# CH32L103K8U-R0.net
KiCad netlist of a schematic drawn in Altium Designer
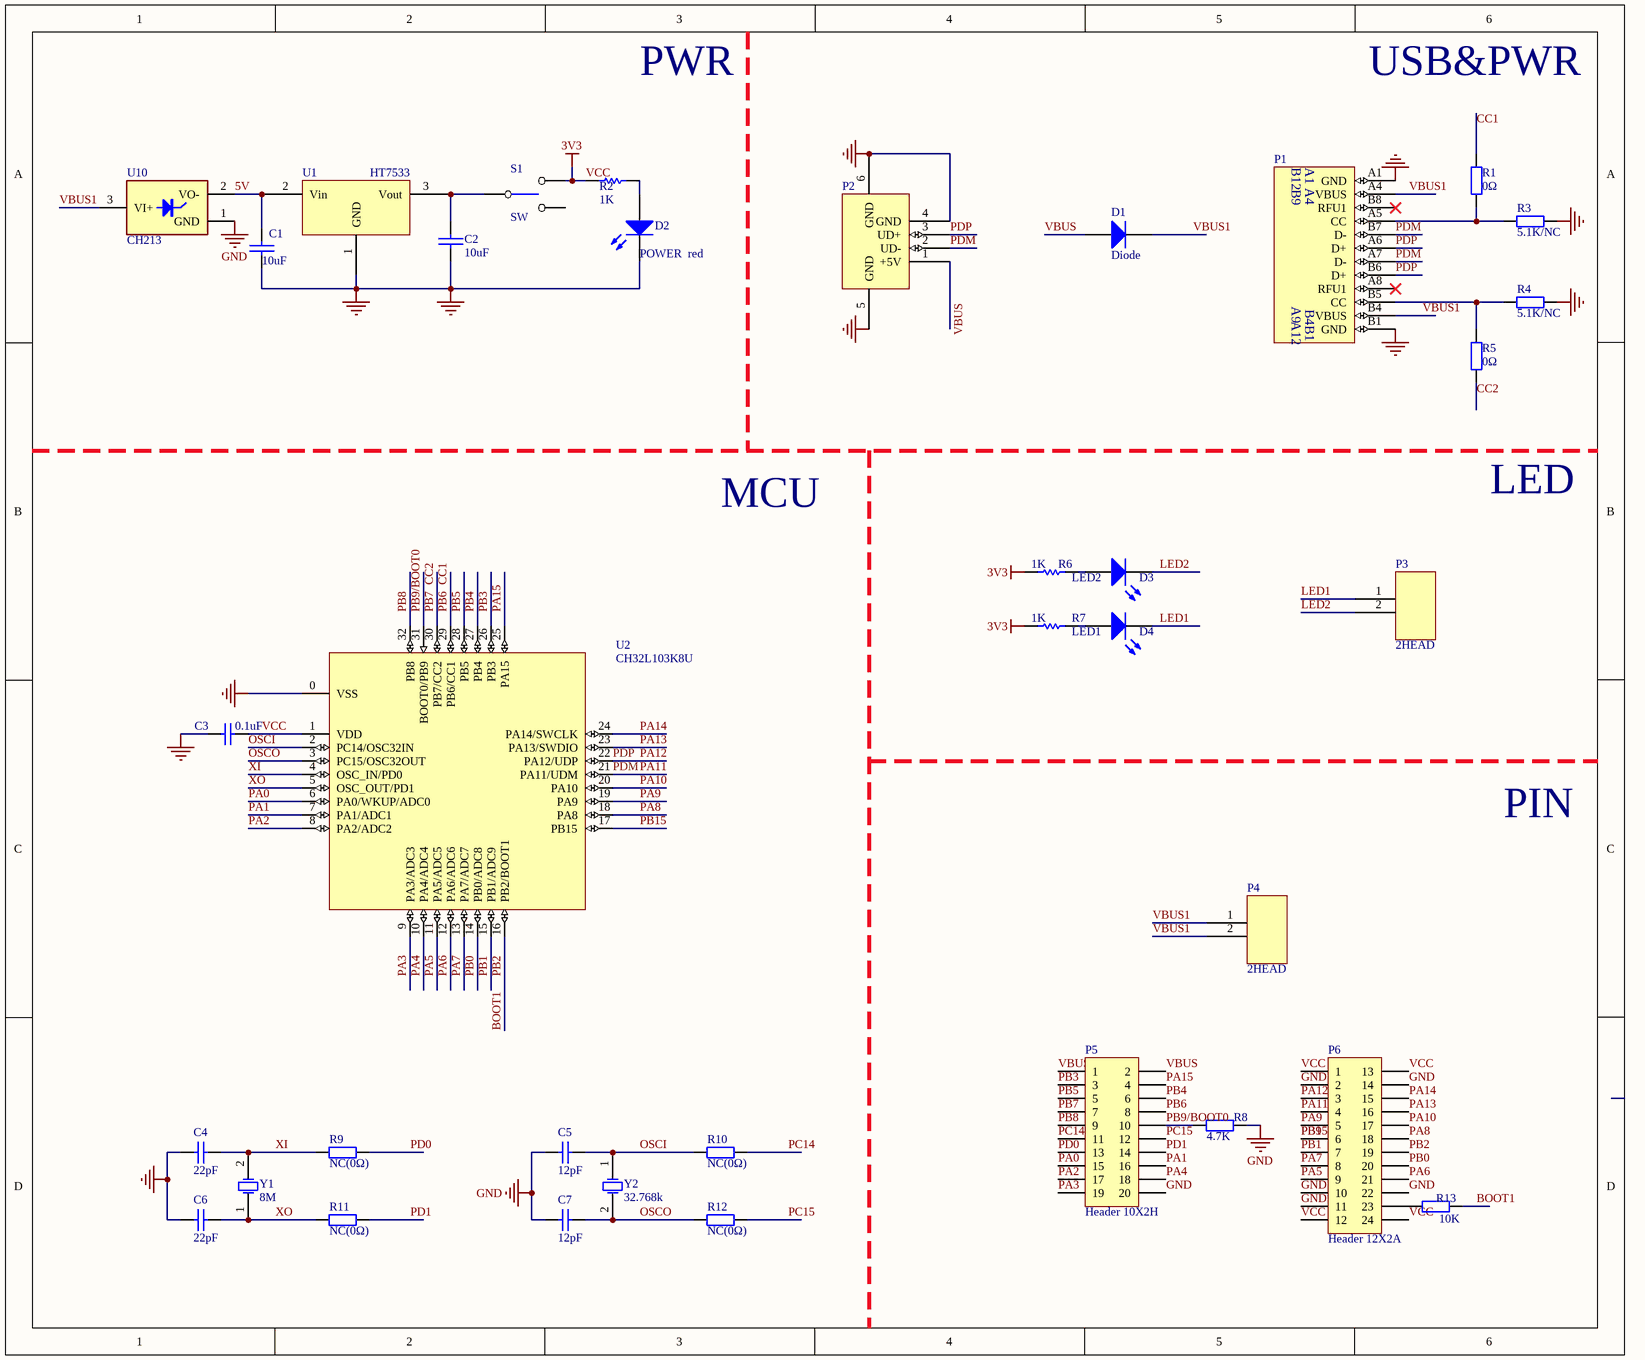
[diagram p0: CH32L103K8U-R0.SchDoc]

(export (version "E")
  (design (tool "Eeschema 10.0.6"))
  (components
    (comp (ref "C1")
      (value "10uF")
      (footprint "0603_C")
      (description "Capacitor")
      (libsource (lib "*") (part "CAP"))
    )
    (comp (ref "C2")
      (value "10uF")
      (footprint "0603_C")
      (description "Capacitor")
      (libsource (lib "*") (part "CAP"))
    )
    (comp (ref "C3")
      (value "0.1uF")
      (footprint "0603_C")
      (description "Capacitor")
      (fields (field (name "PUBLISHER") "Altium Limited"))
      (libsource (lib "*") (part "Cap"))
    )
    (comp (ref "C4")
      (value "22pF")
      (footprint "0603_C")
      (description "Capacitor")
      (fields (field (name "PUBLISHER") "Altium Limited"))
      (libsource (lib "*") (part "Cap"))
    )
    (comp (ref "C5")
      (value "12pF")
      (footprint "0603")
      (description "Capacitor")
      (fields (field (name "PUBLISHER") "Altium Limited"))
      (libsource (lib "Miscellaneous Devices") (part "Cap"))
    )
    (comp (ref "C6")
      (value "22pF")
      (footprint "0603_C")
      (description "Capacitor")
      (fields (field (name "PUBLISHER") "Altium Limited"))
      (libsource (lib "*") (part "Cap"))
    )
    (comp (ref "C7")
      (value "12pF")
      (footprint "0603")
      (description "Capacitor")
      (fields (field (name "PUBLISHER") "Altium Limited"))
      (libsource (lib "Miscellaneous Devices") (part "Cap"))
    )
    (comp (ref "D1")
      (value "Diode")
      (footprint "SOD-123")
      (description "Default Diode")
      (fields (field (name "PUBLISHER") "Altium Limited"))
      (libsource (lib "Miscellaneous Devices") (part "Diode"))
    )
    (comp (ref "D2")
      (value "POWER  red")
      (footprint "0603+")
      (description "Typical INFRARED GaAs LED")
      (fields (field (name "PUBLISHER") "Altium Limited"))
      (libsource (lib "*") (part "LED0"))
    )
    (comp (ref "D3")
      (value "LED2")
      (footprint "0603+")
      (description "Typical INFRARED GaAs LED")
      (fields (field (name "PUBLISHER") "Altium Limited"))
      (libsource (lib "*") (part "LED0"))
    )
    (comp (ref "D4")
      (value "LED1")
      (footprint "0603+")
      (description "Typical INFRARED GaAs LED")
      (fields (field (name "PUBLISHER") "Altium Limited"))
      (libsource (lib "*") (part "LED0"))
    )
    (comp (ref "P1")
      (value "TYPE-C")
      (footprint "TYPE-C-Receptacle-2.0")
      (libsource (lib "*") (part "TYPE-C1"))
    )
    (comp (ref "P2")
      (value "USB_A")
      (footprint "USBAF")
      (description "USB Port")
      (libsource (lib "*") (part "USB"))
    )
    (comp (ref "P3") (value "2HEAD") (footprint "SIP2-2.54mm") (libsource (lib "*") (part "2HEAD")))
    (comp (ref "P4") (value "2HEAD") (footprint "SIP2-2.54mm") (libsource (lib "*") (part "2HEAD")))
    (comp (ref "P5")
      (value "Header 10X2H")
      (footprint "HDR2X10H")
      (description "Header, 10-Pin, Dual row, Right Angle")
      (fields (field (name "PUBLISHER") "Altium Limited"))
      (libsource (lib "Miscellaneous Connectors") (part "Header 10X2H"))
    )
    (comp (ref "P6")
      (value "Header 12X2A")
      (footprint "HDR2X12_CEN")
      (description "Header, 12-Pin, Dual row")
      (fields (field (name "PUBLISHER") "Altium Limited"))
      (libsource (lib "Miscellaneous Connectors") (part "Header 12X2A"))
    )
    (comp (ref "R1")
      (value "0Ω")
      (footprint "0603")
      (description "Resistor")
      (libsource (lib "Miscellaneous Devices") (part "Res2"))
    )
    (comp (ref "R2")
      (value "1K")
      (footprint "0603")
      (description "Semiconductor Resistor")
      (libsource (lib "*") (part "Res Semi"))
    )
    (comp (ref "R3")
      (value "5.1K/NC")
      (footprint "0603")
      (description "Resistor")
      (libsource (lib "") (part "Res2_1"))
    )
    (comp (ref "R4")
      (value "5.1K/NC")
      (footprint "0603")
      (description "Resistor")
      (libsource (lib "") (part "Res2_1"))
    )
    (comp (ref "R5")
      (value "0Ω")
      (footprint "0603")
      (description "Resistor")
      (libsource (lib "Miscellaneous Devices") (part "Res2"))
    )
    (comp (ref "R6")
      (value "1K")
      (footprint "0603")
      (description "Semiconductor Resistor")
      (libsource (lib "*") (part "Res Semi"))
    )
    (comp (ref "R7")
      (value "1K")
      (footprint "0603")
      (description "Semiconductor Resistor")
      (libsource (lib "*") (part "Res Semi"))
    )
    (comp (ref "R8")
      (value "4.7K")
      (footprint "0603")
      (description "Resistor")
      (libsource (lib "") (part "Res2_1"))
    )
    (comp (ref "R9")
      (value "NC(0Ω)")
      (footprint "0603")
      (description "Resistor")
      (libsource (lib "") (part "Res2_2"))
    )
    (comp (ref "R10")
      (value "NC(0Ω)")
      (footprint "0603")
      (description "Resistor")
      (libsource (lib "") (part "Res2_2"))
    )
    (comp (ref "R11")
      (value "NC(0Ω)")
      (footprint "0603")
      (description "Resistor")
      (libsource (lib "") (part "Res2_2"))
    )
    (comp (ref "R12")
      (value "NC(0Ω)")
      (footprint "0603")
      (description "Resistor")
      (libsource (lib "") (part "Res2_2"))
    )
    (comp (ref "R13")
      (value "10K")
      (footprint "0603")
      (description "Resistor")
      (fields (field (name "PUBLISHER") "Altium Limited"))
      (libsource (lib "*") (part "Res2"))
    )
    (comp (ref "S1") (value "SW") (footprint "SW1") (libsource (lib "*") (part "SW")))
    (comp (ref "U1")
      (value "HT7533")
      (footprint "SOT-89")
      (libsource (lib "wch_sch_others") (part "1117-3.3V"))
    )
    (comp (ref "U2")
      (value "CH32L103K8U")
      (footprint "QFN32_4X4")
      (description "RISC-V LMD-MCU, 96MHz, USB, Type-C/PD-5K1, CAN, OPA, lower power")
      (libsource (lib "CHXXX") (part "CH32L103K8U"))
    )
    (comp (ref "U10")
      (value "CH213")
      (footprint "SOT-23-3")
      (description "Ideal Diode 5V*1A")
      (libsource (lib "CHXXX") (part "CH213E"))
    )
    (comp (ref "Y1")
      (value "8M")
      (footprint "XT_AT49")
      (description "Crystal Oscillator")
      (fields (field (name "PUBLISHER") "Altium Limited"))
      (libsource (lib "*") (part "XTAL"))
    )
    (comp (ref "Y2")
      (value "32.768k")
      (footprint "FC-135")
      (description "Crystal Oscillator")
      (fields (field (name "PUBLISHER") "Altium Limited"))
      (libsource (lib "Miscellaneous Devices") (part "XTAL"))
    )
  )
  (nets
    (net (code "1") (name "/5V") (class "Default")
      (node (ref "C1") (pin "1") (pinfunction "1_1") (pintype "passive"))
      (node (ref "U1") (pin "2") (pinfunction "Vin_2") (pintype "passive"))
      (node (ref "U10") (pin "2") (pinfunction "VO-_2") (pintype "power_in"))
    )
    (net (code "3") (name "/BOOT1") (class "Default")
      (node (ref "P6") (pin "19") (pinfunction "19_19") (pintype "passive"))
      (node (ref "R13") (pin "2") (pinfunction "2_2") (pintype "passive"))
      (node (ref "U2") (pin "16") (pinfunction "PB2/BOOT1_16") (pintype "bidirectional"))
    )
    (net (code "4") (name "/CC1") (class "Default")
      (node (ref "P5") (pin "8") (pinfunction "8_8") (pintype "passive"))
      (node (ref "R1") (pin "2") (pinfunction "2_2") (pintype "passive"))
      (node (ref "U2") (pin "29") (pinfunction "PB6/CC1_29") (pintype "bidirectional"))
    )
    (net (code "5") (name "/CC2") (class "Default")
      (node (ref "P5") (pin "7") (pinfunction "7_7") (pintype "passive"))
      (node (ref "R5") (pin "1") (pinfunction "1_1") (pintype "passive"))
      (node (ref "U2") (pin "30") (pinfunction "PB7/CC2_30") (pintype "bidirectional"))
    )
    (net (code "6") (name "/LED1") (class "Default")
      (node (ref "D4") (pin "2") (pinfunction "K_2") (pintype "passive"))
      (node (ref "P3") (pin "1") (pintype "passive"))
    )
    (net (code "7") (name "/LED2") (class "Default")
      (node (ref "D3") (pin "2") (pinfunction "K_2") (pintype "passive"))
      (node (ref "P3") (pin "2") (pintype "passive"))
    )
    (net (code "8") (name "/OSCI") (class "Default")
      (node (ref "C5") (pin "1") (pinfunction "1_1") (pintype "passive"))
      (node (ref "R10") (pin "2") (pinfunction "2_2") (pintype "passive"))
      (node (ref "U2") (pin "2") (pinfunction "PC14/OSC32IN_2") (pintype "bidirectional"))
      (node (ref "Y2") (pin "1") (pinfunction "OSC1_1") (pintype "passive"))
    )
    (net (code "9") (name "/OSCO") (class "Default")
      (node (ref "C7") (pin "1") (pinfunction "1_1") (pintype "passive"))
      (node (ref "R12") (pin "2") (pinfunction "2_2") (pintype "passive"))
      (node (ref "U2") (pin "3") (pinfunction "PC15/OSC32OUT_3") (pintype "bidirectional"))
      (node (ref "Y2") (pin "2") (pinfunction "OSC2_2") (pintype "passive"))
    )
    (net (code "10") (name "/PA0") (class "Default")
      (node (ref "P5") (pin "15") (pinfunction "15_15") (pintype "passive"))
      (node (ref "U2") (pin "6") (pinfunction "PA0/WKUP/ADC0_6") (pintype "bidirectional"))
    )
    (net (code "11") (name "/PA1") (class "Default")
      (node (ref "P5") (pin "16") (pinfunction "16_16") (pintype "passive"))
      (node (ref "U2") (pin "7") (pinfunction "PA1/ADC1_7") (pintype "bidirectional"))
    )
    (net (code "12") (name "/PA2") (class "Default")
      (node (ref "P5") (pin "17") (pinfunction "17_17") (pintype "passive"))
      (node (ref "U2") (pin "8") (pinfunction "PA2/ADC2_8") (pintype "bidirectional"))
    )
    (net (code "13") (name "/PA3") (class "Default")
      (node (ref "P5") (pin "19") (pinfunction "19_19") (pintype "passive"))
      (node (ref "U2") (pin "9") (pinfunction "PA3/ADC3_9") (pintype "bidirectional"))
    )
    (net (code "14") (name "/PA4") (class "Default")
      (node (ref "P5") (pin "18") (pinfunction "18_18") (pintype "passive"))
      (node (ref "U2") (pin "10") (pinfunction "PA4/ADC4_10") (pintype "bidirectional"))
    )
    (net (code "15") (name "/PA5") (class "Default")
      (node (ref "P6") (pin "9") (pinfunction "9_9") (pintype "passive"))
      (node (ref "U2") (pin "11") (pinfunction "PA5/ADC5_11") (pintype "bidirectional"))
    )
    (net (code "16") (name "/PA6") (class "Default")
      (node (ref "P6") (pin "21") (pinfunction "21_21") (pintype "passive"))
      (node (ref "U2") (pin "12") (pinfunction "PA6/ADC6_12") (pintype "bidirectional"))
    )
    (net (code "17") (name "/PA7") (class "Default")
      (node (ref "P6") (pin "8") (pinfunction "8_8") (pintype "passive"))
      (node (ref "U2") (pin "13") (pinfunction "PA7/ADC7_13") (pintype "bidirectional"))
    )
    (net (code "18") (name "/PA8") (class "Default")
      (node (ref "P6") (pin "18") (pinfunction "18_18") (pintype "passive"))
      (node (ref "U2") (pin "18") (pinfunction "PA8_18") (pintype "bidirectional"))
    )
    (net (code "19") (name "/PA9") (class "Default")
      (node (ref "P6") (pin "5") (pinfunction "5_5") (pintype "passive"))
      (node (ref "U2") (pin "19") (pinfunction "PA9_19") (pintype "bidirectional"))
    )
    (net (code "20") (name "/PA10") (class "Default")
      (node (ref "P6") (pin "17") (pinfunction "17_17") (pintype "passive"))
      (node (ref "U2") (pin "20") (pinfunction "PA10_20") (pintype "bidirectional"))
    )
    (net (code "21") (name "/PA11") (class "Default")
      (node (ref "P1") (pin "A7") (pinfunction "D-_A7") (pintype "bidirectional"))
      (node (ref "P1") (pin "B7") (pinfunction "D-_B7") (pintype "bidirectional"))
      (node (ref "P2") (pin "2") (pinfunction "UD-_2") (pintype "bidirectional"))
      (node (ref "P6") (pin "4") (pinfunction "4_4") (pintype "passive"))
      (node (ref "U2") (pin "21") (pinfunction "PA11/UDM_21") (pintype "bidirectional"))
    )
    (net (code "22") (name "/PA12") (class "Default")
      (node (ref "P1") (pin "A6") (pinfunction "D+_A6") (pintype "bidirectional"))
      (node (ref "P1") (pin "B6") (pinfunction "D+_B6") (pintype "bidirectional"))
      (node (ref "P2") (pin "3") (pinfunction "UD+_3") (pintype "bidirectional"))
      (node (ref "P6") (pin "3") (pinfunction "3_3") (pintype "passive"))
      (node (ref "U2") (pin "22") (pinfunction "PA12/UDP_22") (pintype "bidirectional"))
    )
    (net (code "23") (name "/PA13") (class "Default")
      (node (ref "P6") (pin "16") (pinfunction "16_16") (pintype "passive"))
      (node (ref "U2") (pin "23") (pinfunction "PA13/SWDIO_23") (pintype "bidirectional"))
    )
    (net (code "24") (name "/PA14") (class "Default")
      (node (ref "P6") (pin "15") (pinfunction "15_15") (pintype "passive"))
      (node (ref "U2") (pin "24") (pinfunction "PA14/SWCLK_24") (pintype "bidirectional"))
    )
    (net (code "25") (name "/PA15") (class "Default")
      (node (ref "P5") (pin "4") (pinfunction "4_4") (pintype "passive"))
      (node (ref "U2") (pin "25") (pinfunction "PA15_25") (pintype "bidirectional"))
    )
    (net (code "26") (name "/PB0") (class "Default")
      (node (ref "P6") (pin "20") (pinfunction "20_20") (pintype "passive"))
      (node (ref "U2") (pin "14") (pinfunction "PB0/ADC8_14") (pintype "bidirectional"))
    )
    (net (code "27") (name "/PB1") (class "Default")
      (node (ref "P6") (pin "7") (pinfunction "7_7") (pintype "passive"))
      (node (ref "U2") (pin "15") (pinfunction "PB1/ADC9_15") (pintype "bidirectional"))
    )
    (net (code "28") (name "/PB3") (class "Default")
      (node (ref "P5") (pin "3") (pinfunction "3_3") (pintype "passive"))
      (node (ref "U2") (pin "26") (pinfunction "PB3_26") (pintype "bidirectional"))
    )
    (net (code "29") (name "/PB4") (class "Default")
      (node (ref "P5") (pin "6") (pinfunction "6_6") (pintype "passive"))
      (node (ref "U2") (pin "27") (pinfunction "PB4_27") (pintype "bidirectional"))
    )
    (net (code "30") (name "/PB5") (class "Default")
      (node (ref "P5") (pin "5") (pinfunction "5_5") (pintype "passive"))
      (node (ref "U2") (pin "28") (pinfunction "PB5_28") (pintype "bidirectional"))
    )
    (net (code "31") (name "/PB8") (class "Default")
      (node (ref "P5") (pin "9") (pinfunction "9_9") (pintype "passive"))
      (node (ref "U2") (pin "32") (pinfunction "PB8_32") (pintype "bidirectional"))
    )
    (net (code "32") (name "/PB9{slash}BOOT0") (class "Default")
      (node (ref "P5") (pin "10") (pinfunction "10_10") (pintype "passive"))
      (node (ref "R8") (pin "1") (pinfunction "1_1") (pintype "passive"))
      (node (ref "U2") (pin "31") (pinfunction "BOOT0/PB9_31") (pintype "input"))
    )
    (net (code "33") (name "/PB15") (class "Default")
      (node (ref "P6") (pin "6") (pinfunction "6_6") (pintype "passive"))
      (node (ref "U2") (pin "17") (pinfunction "PB15_17") (pintype "bidirectional"))
    )
    (net (code "34") (name "/PC14") (class "Default")
      (node (ref "P5") (pin "11") (pinfunction "11_11") (pintype "passive"))
      (node (ref "R10") (pin "1") (pinfunction "1_1") (pintype "passive"))
    )
    (net (code "35") (name "/PC15") (class "Default")
      (node (ref "P5") (pin "12") (pinfunction "12_12") (pintype "passive"))
      (node (ref "R12") (pin "1") (pinfunction "1_1") (pintype "passive"))
    )
    (net (code "36") (name "/PD0") (class "Default")
      (node (ref "P5") (pin "13") (pinfunction "13_13") (pintype "passive"))
      (node (ref "R9") (pin "1") (pinfunction "1_1") (pintype "passive"))
    )
    (net (code "37") (name "/PD1") (class "Default")
      (node (ref "P5") (pin "14") (pinfunction "14_14") (pintype "passive"))
      (node (ref "R11") (pin "1") (pinfunction "1_1") (pintype "passive"))
    )
    (net (code "38") (name "/VBUS") (class "Default")
      (node (ref "D1") (pin "1") (pinfunction "A_1") (pintype "passive"))
      (node (ref "P2") (pin "1") (pinfunction "+5V_1") (pintype "power_in"))
      (node (ref "P5") (pin "1") (pinfunction "1_1") (pintype "passive"))
      (node (ref "P5") (pin "2") (pinfunction "2_2") (pintype "passive"))
    )
    (net (code "39") (name "/VBUS1") (class "Default")
      (node (ref "D1") (pin "2") (pinfunction "K_2") (pintype "passive"))
      (node (ref "P1") (pin "A4") (pinfunction "VBUS_A4") (pintype "bidirectional"))
      (node (ref "P1") (pin "B4") (pinfunction "VBUS_B4") (pintype "bidirectional"))
      (node (ref "P4") (pin "1") (pintype "passive"))
      (node (ref "P4") (pin "2") (pintype "passive"))
      (node (ref "U10") (pin "3") (pinfunction "VI+_3") (pintype "power_in"))
    )
    (net (code "40") (name "/XI") (class "Default")
      (node (ref "C4") (pin "2") (pinfunction "2_2") (pintype "passive"))
      (node (ref "R9") (pin "2") (pinfunction "2_2") (pintype "passive"))
      (node (ref "U2") (pin "4") (pinfunction "OSC_IN/PD0_4") (pintype "bidirectional"))
      (node (ref "Y1") (pin "2") (pinfunction "OSC2_2") (pintype "passive"))
    )
    (net (code "41") (name "/XO") (class "Default")
      (node (ref "C6") (pin "2") (pinfunction "2_2") (pintype "passive"))
      (node (ref "R11") (pin "2") (pinfunction "2_2") (pintype "passive"))
      (node (ref "U2") (pin "5") (pinfunction "OSC_OUT/PD1_5") (pintype "bidirectional"))
      (node (ref "Y1") (pin "1") (pinfunction "OSC1_1") (pintype "passive"))
    )
    (net (code "42") (name "3V3") (class "Default")
      (node (ref "C3") (pin "1") (pinfunction "1_1") (pintype "passive"))
      (node (ref "P6") (pin "1") (pinfunction "1_1") (pintype "passive"))
      (node (ref "P6") (pin "12") (pinfunction "12_12") (pintype "passive"))
      (node (ref "P6") (pin "13") (pinfunction "13_13") (pintype "passive"))
      (node (ref "P6") (pin "24") (pinfunction "24_24") (pintype "passive"))
      (node (ref "R2") (pin "2") (pinfunction "2_2") (pintype "passive"))
      (node (ref "R6") (pin "1") (pinfunction "1_1") (pintype "passive"))
      (node (ref "R7") (pin "1") (pinfunction "1_1") (pintype "passive"))
      (node (ref "S1") (pin "3") (pinfunction "3_3") (pintype "passive"))
      (node (ref "U2") (pin "1") (pinfunction "VDD_1") (pintype "power_in"))
    )
    (net (code "43") (name "GND") (class "Default")
      (node (ref "C1") (pin "2") (pinfunction "2_2") (pintype "passive"))
      (node (ref "C2") (pin "2") (pinfunction "2_2") (pintype "passive"))
      (node (ref "C3") (pin "2") (pinfunction "2_2") (pintype "passive"))
      (node (ref "C4") (pin "1") (pinfunction "1_1") (pintype "passive"))
      (node (ref "C5") (pin "2") (pinfunction "2_2") (pintype "passive"))
      (node (ref "C6") (pin "1") (pinfunction "1_1") (pintype "passive"))
      (node (ref "C7") (pin "2") (pinfunction "2_2") (pintype "passive"))
      (node (ref "D2") (pin "2") (pinfunction "K_2") (pintype "passive"))
      (node (ref "P1") (pin "A1") (pinfunction "GND_A1") (pintype "bidirectional"))
      (node (ref "P1") (pin "B1") (pinfunction "GND_B1") (pintype "bidirectional"))
      (node (ref "P2") (pin "4") (pinfunction "GND_4") (pintype "power_in"))
      (node (ref "P2") (pin "5") (pinfunction "GND_5") (pintype "power_in"))
      (node (ref "P2") (pin "6") (pinfunction "GND_6") (pintype "power_in"))
      (node (ref "P5") (pin "20") (pinfunction "20_20") (pintype "passive"))
      (node (ref "P6") (pin "10") (pinfunction "10_10") (pintype "passive"))
      (node (ref "P6") (pin "11") (pinfunction "11_11") (pintype "passive"))
      (node (ref "P6") (pin "14") (pinfunction "14_14") (pintype "passive"))
      (node (ref "P6") (pin "2") (pinfunction "2_2") (pintype "passive"))
      (node (ref "P6") (pin "22") (pinfunction "22_22") (pintype "passive"))
      (node (ref "R3") (pin "2") (pinfunction "2_2") (pintype "passive"))
      (node (ref "R4") (pin "2") (pinfunction "2_2") (pintype "passive"))
      (node (ref "R8") (pin "2") (pinfunction "2_2") (pintype "passive"))
      (node (ref "U1") (pin "1") (pinfunction "GND_1") (pintype "passive"))
      (node (ref "U10") (pin "1") (pinfunction "GND_1") (pintype "power_in"))
      (node (ref "U2") (pin "0") (pinfunction "VSS_0") (pintype "power_in"))
    )
    (net (code "44") (name "Net-(D2-A)") (class "Default")
      (node (ref "D2") (pin "1") (pinfunction "A_1") (pintype "passive"))
      (node (ref "R2") (pin "1") (pinfunction "1_1") (pintype "passive"))
    )
    (net (code "45") (name "Net-(D3-A)") (class "Default")
      (node (ref "D3") (pin "1") (pinfunction "A_1") (pintype "passive"))
      (node (ref "R6") (pin "2") (pinfunction "2_2") (pintype "passive"))
    )
    (net (code "46") (name "Net-(D4-A)") (class "Default")
      (node (ref "D4") (pin "1") (pinfunction "A_1") (pintype "passive"))
      (node (ref "R7") (pin "2") (pinfunction "2_2") (pintype "passive"))
    )
    (net (code "47") (name "Net-(P1-CC-PadA5)") (class "Default")
      (node (ref "P1") (pin "A5") (pinfunction "CC_A5") (pintype "bidirectional"))
      (node (ref "R1") (pin "1") (pinfunction "1_1") (pintype "passive"))
      (node (ref "R3") (pin "1") (pinfunction "1_1") (pintype "passive"))
    )
    (net (code "48") (name "Net-(P1-CC-PadB5)") (class "Default")
      (node (ref "P1") (pin "B5") (pinfunction "CC_B5") (pintype "bidirectional"))
      (node (ref "R4") (pin "1") (pinfunction "1_1") (pintype "passive"))
      (node (ref "R5") (pin "2") (pinfunction "2_2") (pintype "passive"))
    )
    (net (code "49") (name "Net-(P6-Pad23)") (class "Default")
      (node (ref "P6") (pin "23") (pinfunction "23_23") (pintype "passive"))
      (node (ref "R13") (pin "1") (pinfunction "1_1") (pintype "passive"))
    )
    (net (code "50") (name "Net-(U1-Vout)") (class "Default")
      (node (ref "C2") (pin "1") (pinfunction "1_1") (pintype "passive"))
      (node (ref "S1") (pin "1") (pinfunction "1_1") (pintype "passive"))
      (node (ref "U1") (pin "3") (pinfunction "Vout_3") (pintype "passive"))
    )
    (net (code "51") (name "unconnected-(P1-RFU1-PadA8)") (class "Default")
      (node (ref "P1") (pin "A8") (pinfunction "RFU1_A8") (pintype "bidirectional+no_connect"))
    )
    (net (code "52") (name "unconnected-(P1-RFU1-PadB8)") (class "Default")
      (node (ref "P1") (pin "B8") (pinfunction "RFU1_B8") (pintype "bidirectional+no_connect"))
    )
    (net (code "53") (name "unconnected-(S1-Pad2)") (class "Default")
      (node (ref "S1") (pin "2") (pinfunction "2_2") (pintype "passive"))
    )
  )
)
